# board.net
KiCad netlist of a schematic drawn in EAGLE
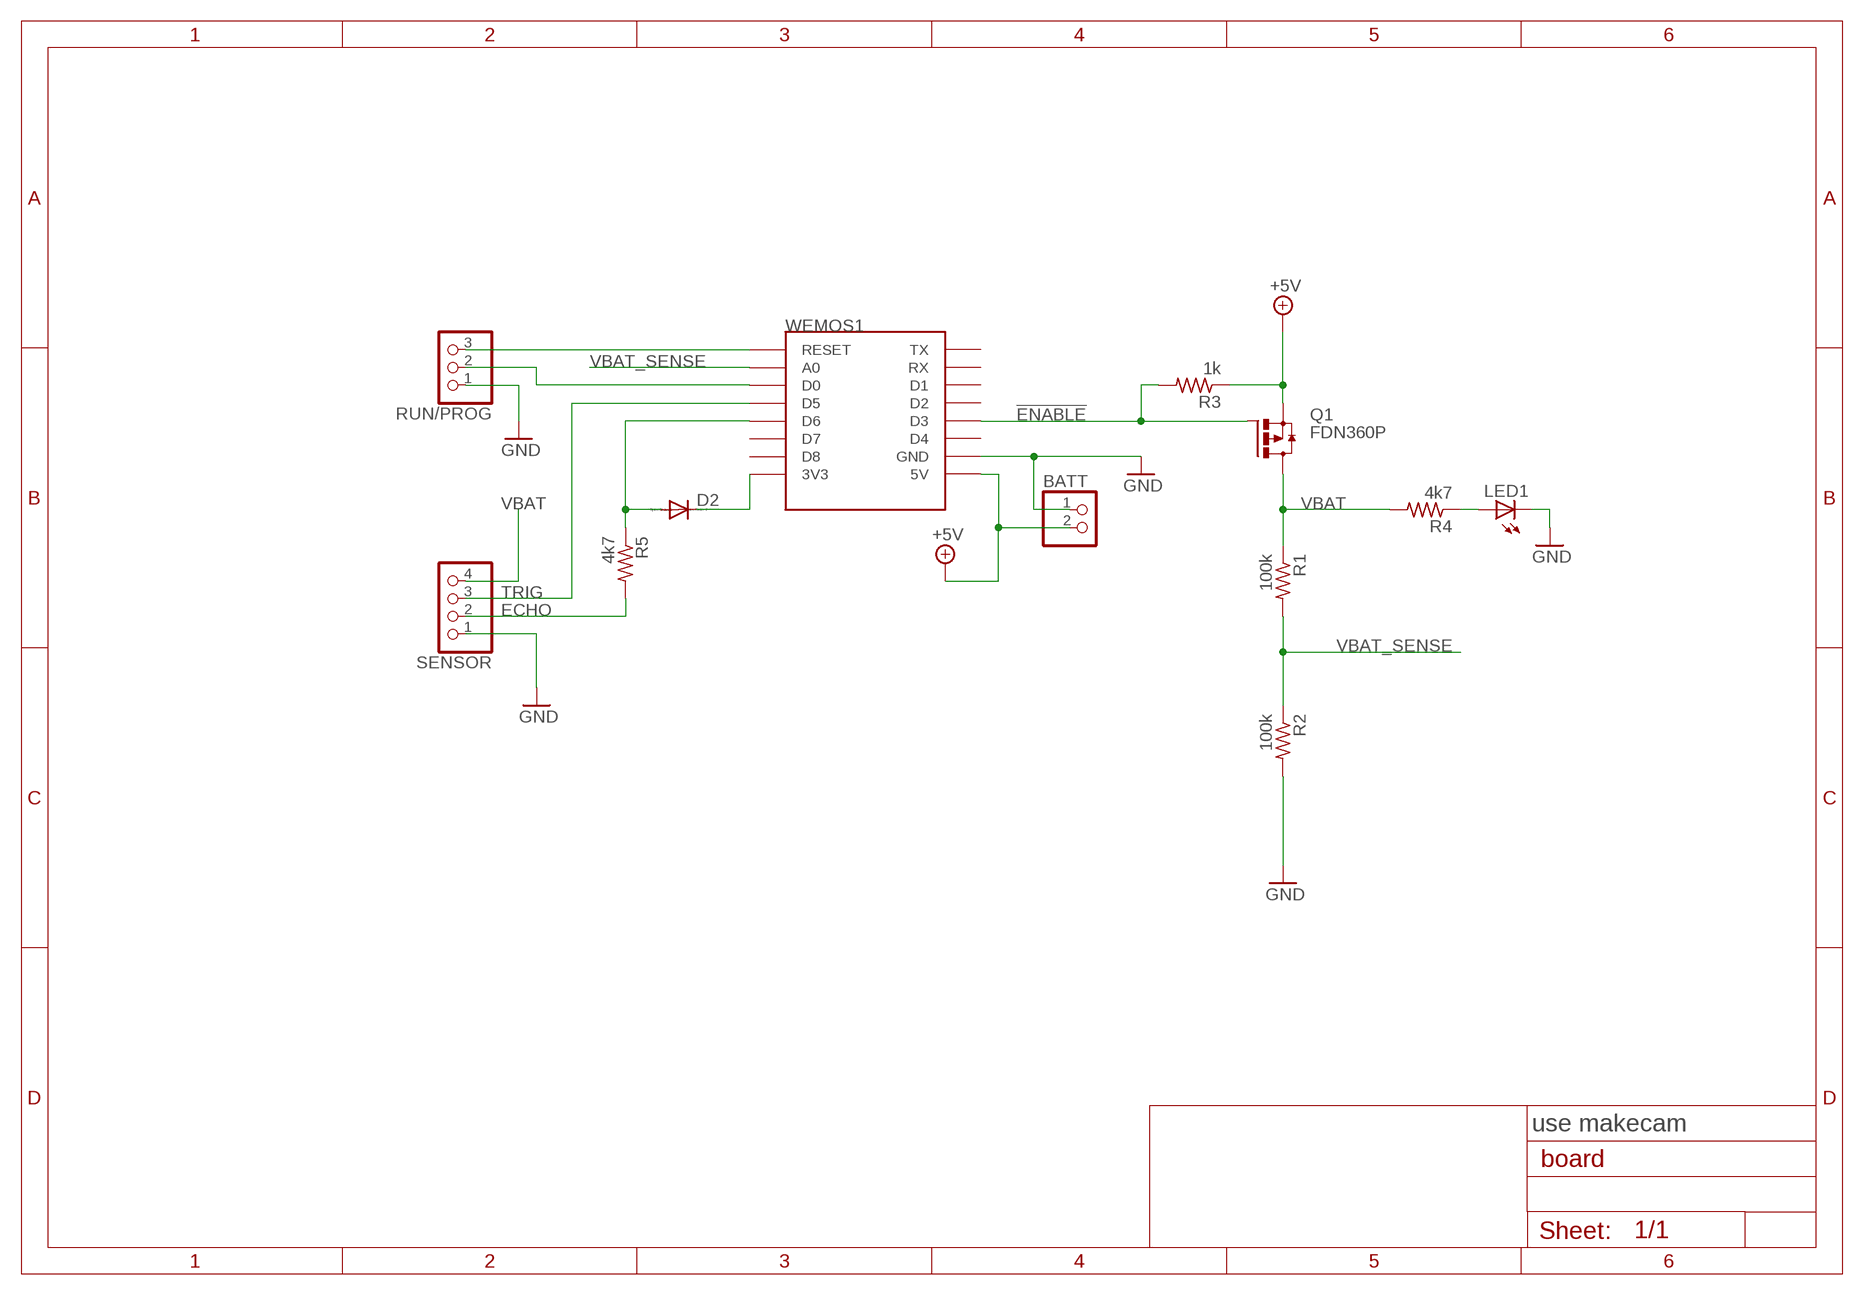
[diagram p0: schematic, sheet 1]

(export (version "E")
  (design (tool "Eeschema 10.0.6"))
  (components
    (comp (ref "BATT")
      (value "PINHD-1X2")
      (footprint "eagle-import:1X02")
      (libsource (lib "eagle-import") (part "PINHD-1X2"))
    )
    (comp (ref "D2")
      (value "DIODE-SOD323-W")
      (footprint "eagle-import:SOD323-W")
      (libsource (lib "eagle-import") (part "DIODE-SOD323-W"))
    )
    (comp (ref "LED1")
      (value "LEDSML1206")
      (footprint "eagle-import:SML1206")
      (libsource (lib "eagle-import") (part "LEDSML1206"))
    )
    (comp (ref "Q1")
      (value "FDN360P")
      (footprint "eagle-import:SUPER-SOT3")
      (libsource (lib "eagle-import") (part "FDN360P"))
    )
    (comp (ref "R1")
      (value "100k")
      (footprint "eagle-import:R0805")
      (libsource (lib "eagle-import") (part "R-US_R0805"))
    )
    (comp (ref "R2")
      (value "100k")
      (footprint "eagle-import:R0805")
      (libsource (lib "eagle-import") (part "R-US_R0805"))
    )
    (comp (ref "R3")
      (value "1k")
      (footprint "eagle-import:R0805")
      (libsource (lib "eagle-import") (part "R-US_R0805"))
    )
    (comp (ref "R4")
      (value "4k7")
      (footprint "eagle-import:R0805")
      (libsource (lib "eagle-import") (part "R-US_R0805"))
    )
    (comp (ref "R5")
      (value "4k7")
      (footprint "eagle-import:R0805")
      (libsource (lib "eagle-import") (part "R-US_R0805"))
    )
    (comp (ref "REV1")
      (value "REVISION")
      (footprint "eagle-import:REVISION")
      (libsource (lib "eagle-import") (part "REVISION"))
    )
    (comp (ref "RUN/PROG")
      (value "PINHD-1X3/90")
      (footprint "eagle-import:1X03_90")
      (libsource (lib "eagle-import") (part "PINHD-1X3/90"))
    )
    (comp (ref "SENSOR")
      (value "PINHD-1X4/90")
      (footprint "eagle-import:1X04_90")
      (libsource (lib "eagle-import") (part "PINHD-1X4/90"))
    )
    (comp (ref "WEMOS1")
      (value "WEMOS-D1-MINI")
      (footprint "eagle-import:WEMOS-D1-MINI")
      (libsource (lib "eagle-import") (part "WEMOS-D1-MINI"))
    )
  )
  (nets
    (net (code "1") (name "+5V") (class "Default")
      (node (ref "BATT") (pin "2") (pinfunction "2_2") (pintype "passive"))
      (node (ref "Q1") (pin "2") (pinfunction "S_2") (pintype "passive"))
      (node (ref "R3") (pin "1") (pinfunction "1_1") (pintype "passive"))
      (node (ref "WEMOS1") (pin "5V") (pinfunction "5V_5V") (pintype "bidirectional"))
    )
    (net (code "2") (name "/ECHO") (class "Default")
      (node (ref "R5") (pin "2") (pinfunction "2_2") (pintype "passive"))
      (node (ref "SENSOR") (pin "2") (pinfunction "2_2") (pintype "passive"))
    )
    (net (code "3") (name "/TRIG") (class "Default")
      (node (ref "SENSOR") (pin "3") (pinfunction "3_3") (pintype "passive"))
      (node (ref "WEMOS1") (pin "D5") (pinfunction "D5_D5") (pintype "bidirectional"))
    )
    (net (code "4") (name "/VBAT") (class "Default")
      (node (ref "Q1") (pin "3") (pinfunction "D_3") (pintype "passive"))
      (node (ref "R1") (pin "1") (pinfunction "1_1") (pintype "passive"))
      (node (ref "R4") (pin "2") (pinfunction "2_2") (pintype "passive"))
      (node (ref "SENSOR") (pin "4") (pinfunction "4_4") (pintype "passive"))
    )
    (net (code "5") (name "/VBAT_SENSE") (class "Default")
      (node (ref "R1") (pin "2") (pinfunction "2_2") (pintype "passive"))
      (node (ref "R2") (pin "1") (pinfunction "1_1") (pintype "passive"))
      (node (ref "WEMOS1") (pin "A0") (pinfunction "A0_A0") (pintype "bidirectional"))
    )
    (net (code "6") (name "/~{ENABLE}") (class "Default")
      (node (ref "Q1") (pin "1") (pinfunction "G_1") (pintype "passive"))
      (node (ref "R3") (pin "2") (pinfunction "2_2") (pintype "passive"))
      (node (ref "WEMOS1") (pin "D3") (pinfunction "D3_D3") (pintype "bidirectional"))
    )
    (net (code "7") (name "GND") (class "Default")
      (node (ref "BATT") (pin "1") (pinfunction "1_1") (pintype "passive"))
      (node (ref "LED1") (pin "C") (pinfunction "C_C") (pintype "passive"))
      (node (ref "R2") (pin "2") (pinfunction "2_2") (pintype "passive"))
      (node (ref "RUN/PROG") (pin "1") (pinfunction "1_1") (pintype "passive"))
      (node (ref "SENSOR") (pin "1") (pinfunction "1_1") (pintype "passive"))
      (node (ref "WEMOS1") (pin "GND") (pinfunction "GND_GND") (pintype "bidirectional"))
    )
    (net (code "8") (name "Net-(D2-PadA)") (class "Default")
      (node (ref "D2") (pin "A") (pinfunction "A_A") (pintype "passive"))
      (node (ref "R5") (pin "1") (pinfunction "1_1") (pintype "passive"))
      (node (ref "WEMOS1") (pin "D6") (pinfunction "D6_D6") (pintype "bidirectional"))
    )
    (net (code "9") (name "Net-(D2-PadC)") (class "Default")
      (node (ref "D2") (pin "C") (pinfunction "C_C") (pintype "passive"))
      (node (ref "WEMOS1") (pin "3V3") (pinfunction "3V3_3V3") (pintype "bidirectional"))
    )
    (net (code "10") (name "Net-(LED1-PadA)") (class "Default")
      (node (ref "LED1") (pin "A") (pinfunction "A_A") (pintype "passive"))
      (node (ref "R4") (pin "1") (pinfunction "1_1") (pintype "passive"))
    )
    (net (code "11") (name "Net-(RUN/PROG-Pad2)") (class "Default")
      (node (ref "RUN/PROG") (pin "2") (pinfunction "2_2") (pintype "passive"))
      (node (ref "WEMOS1") (pin "D0") (pinfunction "D0_D0") (pintype "bidirectional"))
    )
    (net (code "12") (name "Net-(RUN/PROG-Pad3)") (class "Default")
      (node (ref "RUN/PROG") (pin "3") (pinfunction "3_3") (pintype "passive"))
      (node (ref "WEMOS1") (pin "RESET") (pinfunction "RESET_RESET") (pintype "bidirectional"))
    )
    (net (code "13") (name "unconnected-(WEMOS1-PadD1)") (class "Default")
      (node (ref "WEMOS1") (pin "D1") (pinfunction "D1_D1") (pintype "bidirectional"))
    )
    (net (code "14") (name "unconnected-(WEMOS1-PadD2)") (class "Default")
      (node (ref "WEMOS1") (pin "D2") (pinfunction "D2_D2") (pintype "bidirectional"))
    )
    (net (code "15") (name "unconnected-(WEMOS1-PadD4)") (class "Default")
      (node (ref "WEMOS1") (pin "D4") (pinfunction "D4_D4") (pintype "bidirectional"))
    )
    (net (code "16") (name "unconnected-(WEMOS1-PadD7)") (class "Default")
      (node (ref "WEMOS1") (pin "D7") (pinfunction "D7_D7") (pintype "bidirectional"))
    )
    (net (code "17") (name "unconnected-(WEMOS1-PadD8)") (class "Default")
      (node (ref "WEMOS1") (pin "D8") (pinfunction "D8_D8") (pintype "bidirectional"))
    )
    (net (code "18") (name "unconnected-(WEMOS1-PadRX)") (class "Default")
      (node (ref "WEMOS1") (pin "RX") (pinfunction "RX_RX") (pintype "bidirectional"))
    )
    (net (code "19") (name "unconnected-(WEMOS1-PadTX)") (class "Default")
      (node (ref "WEMOS1") (pin "TX") (pinfunction "TX_TX") (pintype "bidirectional"))
    )
  )
)
